# R107B.net
KiCad netlist of a schematic drawn in EAGLE
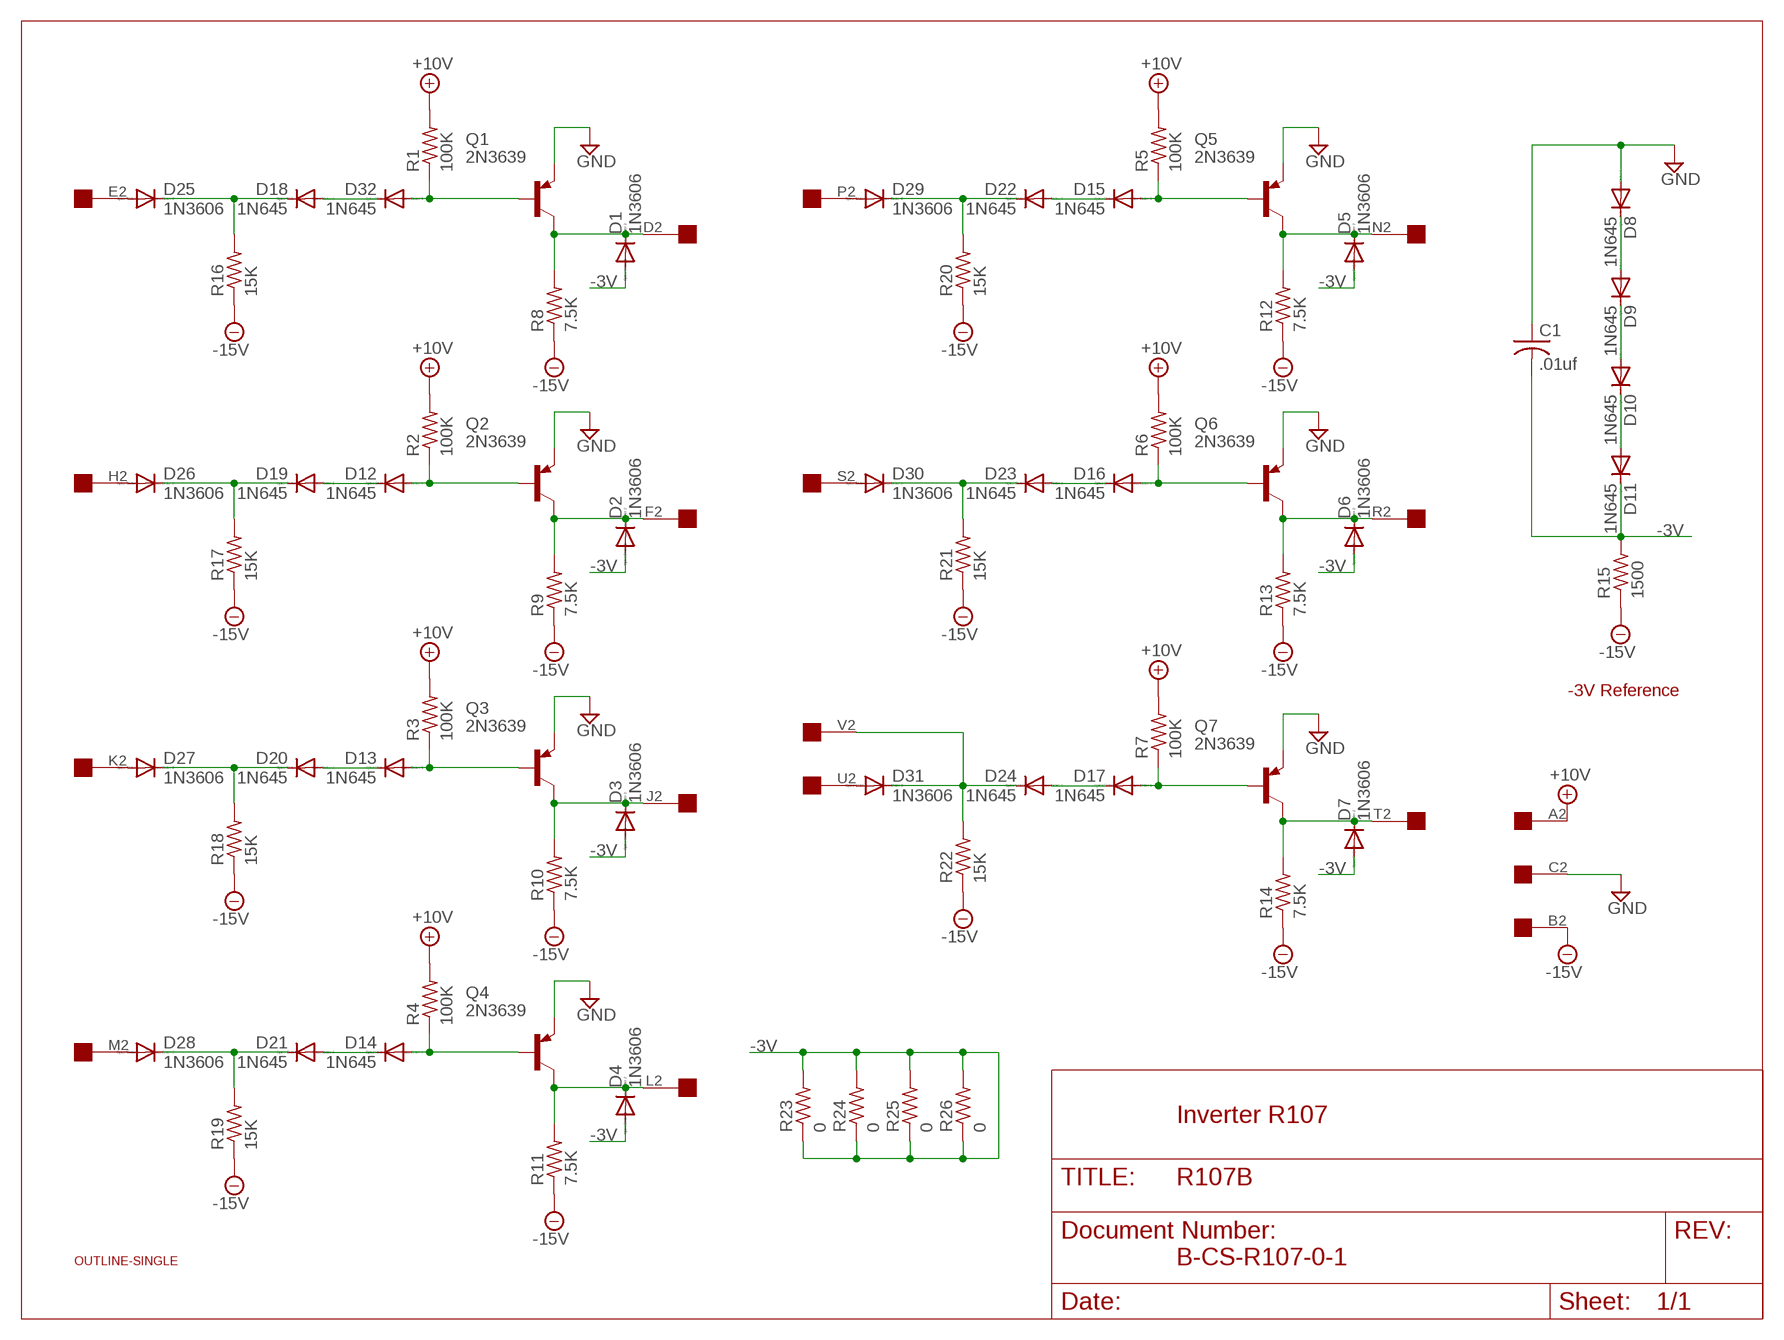
[diagram p0: schematic, sheet 1]

(export (version "E")
  (design (tool "Eeschema 10.0.6"))
  (components
    (comp (ref "C1")
      (value ".01uf")
      (footprint "eagle-import:C063-025X075")
      (libsource (lib "eagle-import") (part "C-US"))
    )
    (comp (ref "D1")
      (value "1N3606")
      (footprint "eagle-import:DO35-10")
      (libsource (lib "eagle-import") (part "1N4148DO35-10"))
    )
    (comp (ref "D2")
      (value "1N3606")
      (footprint "eagle-import:DO35-10")
      (libsource (lib "eagle-import") (part "1N4148DO35-10"))
    )
    (comp (ref "D3")
      (value "1N3606")
      (footprint "eagle-import:DO35-10")
      (libsource (lib "eagle-import") (part "1N4148DO35-10"))
    )
    (comp (ref "D4")
      (value "1N3606")
      (footprint "eagle-import:DO35-10")
      (libsource (lib "eagle-import") (part "1N4148DO35-10"))
    )
    (comp (ref "D5")
      (value "1N3606")
      (footprint "eagle-import:DO35-10")
      (libsource (lib "eagle-import") (part "1N4148DO35-10"))
    )
    (comp (ref "D6")
      (value "1N3606")
      (footprint "eagle-import:DO35-10")
      (libsource (lib "eagle-import") (part "1N4148DO35-10"))
    )
    (comp (ref "D7")
      (value "1N3606")
      (footprint "eagle-import:DO35-10")
      (libsource (lib "eagle-import") (part "1N4148DO35-10"))
    )
    (comp (ref "D8")
      (value "1N645")
      (footprint "eagle-import:DO35-10")
      (libsource (lib "eagle-import") (part "1N4148DO35-10"))
    )
    (comp (ref "D9")
      (value "1N645")
      (footprint "eagle-import:DO35-10")
      (libsource (lib "eagle-import") (part "1N4148DO35-10"))
    )
    (comp (ref "D10")
      (value "1N645")
      (footprint "eagle-import:DO35-10")
      (libsource (lib "eagle-import") (part "1N4148DO35-10"))
    )
    (comp (ref "D11")
      (value "1N645")
      (footprint "eagle-import:DO35-10")
      (libsource (lib "eagle-import") (part "1N4148DO35-10"))
    )
    (comp (ref "D12")
      (value "1N645")
      (footprint "eagle-import:DO35-10")
      (libsource (lib "eagle-import") (part "1N4148DO35-10"))
    )
    (comp (ref "D13")
      (value "1N645")
      (footprint "eagle-import:DO35-10")
      (libsource (lib "eagle-import") (part "1N4148DO35-10"))
    )
    (comp (ref "D14")
      (value "1N645")
      (footprint "eagle-import:DO35-10")
      (libsource (lib "eagle-import") (part "1N4148DO35-10"))
    )
    (comp (ref "D15")
      (value "1N645")
      (footprint "eagle-import:DO35-10")
      (libsource (lib "eagle-import") (part "1N4148DO35-10"))
    )
    (comp (ref "D16")
      (value "1N645")
      (footprint "eagle-import:DO35-10")
      (libsource (lib "eagle-import") (part "1N4148DO35-10"))
    )
    (comp (ref "D17")
      (value "1N645")
      (footprint "eagle-import:DO35-10")
      (libsource (lib "eagle-import") (part "1N4148DO35-10"))
    )
    (comp (ref "D18")
      (value "1N645")
      (footprint "eagle-import:DO35-10")
      (libsource (lib "eagle-import") (part "1N4148DO35-10"))
    )
    (comp (ref "D19")
      (value "1N645")
      (footprint "eagle-import:DO35-10")
      (libsource (lib "eagle-import") (part "1N4148DO35-10"))
    )
    (comp (ref "D20")
      (value "1N645")
      (footprint "eagle-import:DO35-10")
      (libsource (lib "eagle-import") (part "1N4148DO35-10"))
    )
    (comp (ref "D21")
      (value "1N645")
      (footprint "eagle-import:DO35-10")
      (libsource (lib "eagle-import") (part "1N4148DO35-10"))
    )
    (comp (ref "D22")
      (value "1N645")
      (footprint "eagle-import:DO35-10")
      (libsource (lib "eagle-import") (part "1N4148DO35-10"))
    )
    (comp (ref "D23")
      (value "1N645")
      (footprint "eagle-import:DO35-10")
      (libsource (lib "eagle-import") (part "1N4148DO35-10"))
    )
    (comp (ref "D24")
      (value "1N645")
      (footprint "eagle-import:DO35-10")
      (libsource (lib "eagle-import") (part "1N4148DO35-10"))
    )
    (comp (ref "D25")
      (value "1N3606")
      (footprint "eagle-import:DO35-10")
      (libsource (lib "eagle-import") (part "1N4148DO35-10"))
    )
    (comp (ref "D26")
      (value "1N3606")
      (footprint "eagle-import:DO35-10")
      (libsource (lib "eagle-import") (part "1N4148DO35-10"))
    )
    (comp (ref "D27")
      (value "1N3606")
      (footprint "eagle-import:DO35-10")
      (libsource (lib "eagle-import") (part "1N4148DO35-10"))
    )
    (comp (ref "D28")
      (value "1N3606")
      (footprint "eagle-import:DO35-10")
      (libsource (lib "eagle-import") (part "1N4148DO35-10"))
    )
    (comp (ref "D29")
      (value "1N3606")
      (footprint "eagle-import:DO35-10")
      (libsource (lib "eagle-import") (part "1N4148DO35-10"))
    )
    (comp (ref "D30")
      (value "1N3606")
      (footprint "eagle-import:DO35-10")
      (libsource (lib "eagle-import") (part "1N4148DO35-10"))
    )
    (comp (ref "D31")
      (value "1N3606")
      (footprint "eagle-import:DO35-10")
      (libsource (lib "eagle-import") (part "1N4148DO35-10"))
    )
    (comp (ref "D32")
      (value "1N645")
      (footprint "eagle-import:DO35-10")
      (libsource (lib "eagle-import") (part "1N4148DO35-10"))
    )
    (comp (ref "Q1")
      (value "2N3639")
      (footprint "eagle-import:TO39")
      (libsource (lib "eagle-import") (part "2N3637"))
    )
    (comp (ref "Q2")
      (value "2N3639")
      (footprint "eagle-import:TO39")
      (libsource (lib "eagle-import") (part "2N3637"))
    )
    (comp (ref "Q3")
      (value "2N3639")
      (footprint "eagle-import:TO39")
      (libsource (lib "eagle-import") (part "2N3637"))
    )
    (comp (ref "Q4")
      (value "2N3639")
      (footprint "eagle-import:TO39")
      (libsource (lib "eagle-import") (part "2N3637"))
    )
    (comp (ref "Q5")
      (value "2N3639")
      (footprint "eagle-import:TO39")
      (libsource (lib "eagle-import") (part "2N3637"))
    )
    (comp (ref "Q6")
      (value "2N3639")
      (footprint "eagle-import:TO39")
      (libsource (lib "eagle-import") (part "2N3637"))
    )
    (comp (ref "Q7")
      (value "2N3639")
      (footprint "eagle-import:TO39")
      (libsource (lib "eagle-import") (part "2N3637"))
    )
    (comp (ref "R1")
      (value "100K")
      (footprint "eagle-import:0207_10")
      (libsource (lib "eagle-import") (part "R-US_0207/10"))
    )
    (comp (ref "R2")
      (value "100K")
      (footprint "eagle-import:0207_10")
      (libsource (lib "eagle-import") (part "R-US_0207/10"))
    )
    (comp (ref "R3")
      (value "100K")
      (footprint "eagle-import:0207_10")
      (libsource (lib "eagle-import") (part "R-US_0207/10"))
    )
    (comp (ref "R4")
      (value "100K")
      (footprint "eagle-import:0207_10")
      (libsource (lib "eagle-import") (part "R-US_0207/10"))
    )
    (comp (ref "R5")
      (value "100K")
      (footprint "eagle-import:0207_10")
      (libsource (lib "eagle-import") (part "R-US_0207/10"))
    )
    (comp (ref "R6")
      (value "100K")
      (footprint "eagle-import:0207_10")
      (libsource (lib "eagle-import") (part "R-US_0207/10"))
    )
    (comp (ref "R7")
      (value "100K")
      (footprint "eagle-import:0207_10")
      (libsource (lib "eagle-import") (part "R-US_0207/10"))
    )
    (comp (ref "R8")
      (value "7.5K")
      (footprint "eagle-import:0207_10")
      (libsource (lib "eagle-import") (part "R-US_0207/10"))
    )
    (comp (ref "R9")
      (value "7.5K")
      (footprint "eagle-import:0207_10")
      (libsource (lib "eagle-import") (part "R-US_0207/10"))
    )
    (comp (ref "R10")
      (value "7.5K")
      (footprint "eagle-import:0207_10")
      (libsource (lib "eagle-import") (part "R-US_0207/10"))
    )
    (comp (ref "R11")
      (value "7.5K")
      (footprint "eagle-import:0207_10")
      (libsource (lib "eagle-import") (part "R-US_0207/10"))
    )
    (comp (ref "R12")
      (value "7.5K")
      (footprint "eagle-import:0207_10")
      (libsource (lib "eagle-import") (part "R-US_0207/10"))
    )
    (comp (ref "R13")
      (value "7.5K")
      (footprint "eagle-import:0207_10")
      (libsource (lib "eagle-import") (part "R-US_0207/10"))
    )
    (comp (ref "R14")
      (value "7.5K")
      (footprint "eagle-import:0207_10")
      (libsource (lib "eagle-import") (part "R-US_0207/10"))
    )
    (comp (ref "R15")
      (value "1500")
      (footprint "eagle-import:0207_10")
      (libsource (lib "eagle-import") (part "R-US_0207/10"))
    )
    (comp (ref "R16")
      (value "15K")
      (footprint "eagle-import:0207_10")
      (libsource (lib "eagle-import") (part "R-US_0207/10"))
    )
    (comp (ref "R17")
      (value "15K")
      (footprint "eagle-import:0207_10")
      (libsource (lib "eagle-import") (part "R-US_0207/10"))
    )
    (comp (ref "R18")
      (value "15K")
      (footprint "eagle-import:0207_10")
      (libsource (lib "eagle-import") (part "R-US_0207/10"))
    )
    (comp (ref "R19")
      (value "15K")
      (footprint "eagle-import:0207_10")
      (libsource (lib "eagle-import") (part "R-US_0207/10"))
    )
    (comp (ref "R20")
      (value "15K")
      (footprint "eagle-import:0207_10")
      (libsource (lib "eagle-import") (part "R-US_0207/10"))
    )
    (comp (ref "R21")
      (value "15K")
      (footprint "eagle-import:0207_10")
      (libsource (lib "eagle-import") (part "R-US_0207/10"))
    )
    (comp (ref "R22")
      (value "15K")
      (footprint "eagle-import:0207_10")
      (libsource (lib "eagle-import") (part "R-US_0207/10"))
    )
    (comp (ref "R23")
      (value "0")
      (footprint "eagle-import:0207_10")
      (libsource (lib "eagle-import") (part "R-US_0207/10"))
    )
    (comp (ref "R24")
      (value "0")
      (footprint "eagle-import:0207_10")
      (libsource (lib "eagle-import") (part "R-US_0207/10"))
    )
    (comp (ref "R25")
      (value "0")
      (footprint "eagle-import:0207_10")
      (libsource (lib "eagle-import") (part "R-US_0207/10"))
    )
    (comp (ref "R26")
      (value "0")
      (footprint "eagle-import:0207_10")
      (libsource (lib "eagle-import") (part "R-US_0207/10"))
    )
    (comp (ref "U$1")
      (value "OUTLINE-SINGLE")
      (footprint "eagle-import:SINGLE")
      (libsource (lib "eagle-import") (part "OUTLINE-SINGLE"))
    )
    (comp (ref "U$2")
      (value "EDGE-1")
      (footprint "eagle-import:EDGE-CON1")
      (libsource (lib "eagle-import") (part "EDGE-1"))
    )
  )
  (nets
    (net (code "1") (name "+10V") (class "Default")
      (node (ref "R1") (pin "2") (pinfunction "2_2") (pintype "passive"))
      (node (ref "R2") (pin "2") (pinfunction "2_2") (pintype "passive"))
      (node (ref "R3") (pin "2") (pinfunction "2_2") (pintype "passive"))
      (node (ref "R4") (pin "2") (pinfunction "2_2") (pintype "passive"))
      (node (ref "R5") (pin "2") (pinfunction "2_2") (pintype "passive"))
      (node (ref "R6") (pin "2") (pinfunction "2_2") (pintype "passive"))
      (node (ref "R7") (pin "2") (pinfunction "2_2") (pintype "passive"))
      (node (ref "U$2") (pin "A2") (pinfunction "1_A2") (pintype "bidirectional"))
    )
    (net (code "2") (name "-15V") (class "Default")
      (node (ref "R10") (pin "1") (pinfunction "1_1") (pintype "passive"))
      (node (ref "R11") (pin "1") (pinfunction "1_1") (pintype "passive"))
      (node (ref "R12") (pin "1") (pinfunction "1_1") (pintype "passive"))
      (node (ref "R13") (pin "1") (pinfunction "1_1") (pintype "passive"))
      (node (ref "R14") (pin "1") (pinfunction "1_1") (pintype "passive"))
      (node (ref "R15") (pin "1") (pinfunction "1_1") (pintype "passive"))
      (node (ref "R16") (pin "1") (pinfunction "1_1") (pintype "passive"))
      (node (ref "R17") (pin "1") (pinfunction "1_1") (pintype "passive"))
      (node (ref "R18") (pin "1") (pinfunction "1_1") (pintype "passive"))
      (node (ref "R19") (pin "1") (pinfunction "1_1") (pintype "passive"))
      (node (ref "R20") (pin "1") (pinfunction "1_1") (pintype "passive"))
      (node (ref "R21") (pin "1") (pinfunction "1_1") (pintype "passive"))
      (node (ref "R22") (pin "1") (pinfunction "1_1") (pintype "passive"))
      (node (ref "R8") (pin "1") (pinfunction "1_1") (pintype "passive"))
      (node (ref "R9") (pin "1") (pinfunction "1_1") (pintype "passive"))
      (node (ref "U$2") (pin "B2") (pinfunction "1_B2") (pintype "bidirectional"))
    )
    (net (code "3") (name "/-3V") (class "Default")
      (node (ref "C1") (pin "2") (pinfunction "2_2") (pintype "passive"))
      (node (ref "D1") (pin "A") (pinfunction "A_A") (pintype "passive"))
      (node (ref "D11") (pin "C") (pinfunction "C_C") (pintype "passive"))
      (node (ref "D2") (pin "A") (pinfunction "A_A") (pintype "passive"))
      (node (ref "D3") (pin "A") (pinfunction "A_A") (pintype "passive"))
      (node (ref "D4") (pin "A") (pinfunction "A_A") (pintype "passive"))
      (node (ref "D5") (pin "A") (pinfunction "A_A") (pintype "passive"))
      (node (ref "D6") (pin "A") (pinfunction "A_A") (pintype "passive"))
      (node (ref "D7") (pin "A") (pinfunction "A_A") (pintype "passive"))
      (node (ref "R15") (pin "2") (pinfunction "2_2") (pintype "passive"))
      (node (ref "R23") (pin "1") (pinfunction "1_1") (pintype "passive"))
      (node (ref "R23") (pin "2") (pinfunction "2_2") (pintype "passive"))
      (node (ref "R24") (pin "1") (pinfunction "1_1") (pintype "passive"))
      (node (ref "R24") (pin "2") (pinfunction "2_2") (pintype "passive"))
      (node (ref "R25") (pin "1") (pinfunction "1_1") (pintype "passive"))
      (node (ref "R25") (pin "2") (pinfunction "2_2") (pintype "passive"))
      (node (ref "R26") (pin "1") (pinfunction "1_1") (pintype "passive"))
      (node (ref "R26") (pin "2") (pinfunction "2_2") (pintype "passive"))
    )
    (net (code "4") (name "GND") (class "Default")
      (node (ref "C1") (pin "1") (pinfunction "1_1") (pintype "passive"))
      (node (ref "D8") (pin "A") (pinfunction "A_A") (pintype "passive"))
      (node (ref "Q1") (pin "1") (pinfunction "E_1") (pintype "passive"))
      (node (ref "Q2") (pin "1") (pinfunction "E_1") (pintype "passive"))
      (node (ref "Q3") (pin "1") (pinfunction "E_1") (pintype "passive"))
      (node (ref "Q4") (pin "1") (pinfunction "E_1") (pintype "passive"))
      (node (ref "Q5") (pin "1") (pinfunction "E_1") (pintype "passive"))
      (node (ref "Q6") (pin "1") (pinfunction "E_1") (pintype "passive"))
      (node (ref "Q7") (pin "1") (pinfunction "E_1") (pintype "passive"))
      (node (ref "U$2") (pin "C2") (pinfunction "1_C2") (pintype "bidirectional"))
    )
    (net (code "5") (name "Net-(D8-PadC)") (class "Default")
      (node (ref "D8") (pin "C") (pinfunction "C_C") (pintype "passive"))
      (node (ref "D9") (pin "A") (pinfunction "A_A") (pintype "passive"))
    )
    (net (code "6") (name "Net-(D10-PadA)") (class "Default")
      (node (ref "D10") (pin "A") (pinfunction "A_A") (pintype "passive"))
      (node (ref "D9") (pin "C") (pinfunction "C_C") (pintype "passive"))
    )
    (net (code "7") (name "Net-(D10-PadC)") (class "Default")
      (node (ref "D10") (pin "C") (pinfunction "C_C") (pintype "passive"))
      (node (ref "D11") (pin "A") (pinfunction "A_A") (pintype "passive"))
    )
    (net (code "8") (name "Net-(D12-PadC)") (class "Default")
      (node (ref "D12") (pin "C") (pinfunction "C_C") (pintype "passive"))
      (node (ref "D19") (pin "A") (pinfunction "A_A") (pintype "passive"))
    )
    (net (code "9") (name "Net-(D13-PadC)") (class "Default")
      (node (ref "D13") (pin "C") (pinfunction "C_C") (pintype "passive"))
      (node (ref "D20") (pin "A") (pinfunction "A_A") (pintype "passive"))
    )
    (net (code "10") (name "Net-(D14-PadC)") (class "Default")
      (node (ref "D14") (pin "C") (pinfunction "C_C") (pintype "passive"))
      (node (ref "D21") (pin "A") (pinfunction "A_A") (pintype "passive"))
    )
    (net (code "11") (name "Net-(D15-PadC)") (class "Default")
      (node (ref "D15") (pin "C") (pinfunction "C_C") (pintype "passive"))
      (node (ref "D22") (pin "A") (pinfunction "A_A") (pintype "passive"))
    )
    (net (code "12") (name "Net-(D16-PadC)") (class "Default")
      (node (ref "D16") (pin "C") (pinfunction "C_C") (pintype "passive"))
      (node (ref "D23") (pin "A") (pinfunction "A_A") (pintype "passive"))
    )
    (net (code "13") (name "Net-(D17-PadC)") (class "Default")
      (node (ref "D17") (pin "C") (pinfunction "C_C") (pintype "passive"))
      (node (ref "D24") (pin "A") (pinfunction "A_A") (pintype "passive"))
    )
    (net (code "14") (name "Net-(D18-PadA)") (class "Default")
      (node (ref "D18") (pin "A") (pinfunction "A_A") (pintype "passive"))
      (node (ref "D32") (pin "C") (pinfunction "C_C") (pintype "passive"))
    )
    (net (code "15") (name "Net-(D18-PadC)") (class "Default")
      (node (ref "D18") (pin "C") (pinfunction "C_C") (pintype "passive"))
      (node (ref "D25") (pin "C") (pinfunction "C_C") (pintype "passive"))
      (node (ref "R16") (pin "2") (pinfunction "2_2") (pintype "passive"))
    )
    (net (code "16") (name "Net-(D19-PadC)") (class "Default")
      (node (ref "D19") (pin "C") (pinfunction "C_C") (pintype "passive"))
      (node (ref "D26") (pin "C") (pinfunction "C_C") (pintype "passive"))
      (node (ref "R17") (pin "2") (pinfunction "2_2") (pintype "passive"))
    )
    (net (code "17") (name "Net-(D20-PadC)") (class "Default")
      (node (ref "D20") (pin "C") (pinfunction "C_C") (pintype "passive"))
      (node (ref "D27") (pin "C") (pinfunction "C_C") (pintype "passive"))
      (node (ref "R18") (pin "2") (pinfunction "2_2") (pintype "passive"))
    )
    (net (code "18") (name "Net-(D21-PadC)") (class "Default")
      (node (ref "D21") (pin "C") (pinfunction "C_C") (pintype "passive"))
      (node (ref "D28") (pin "C") (pinfunction "C_C") (pintype "passive"))
      (node (ref "R19") (pin "2") (pinfunction "2_2") (pintype "passive"))
    )
    (net (code "19") (name "Net-(D22-PadC)") (class "Default")
      (node (ref "D22") (pin "C") (pinfunction "C_C") (pintype "passive"))
      (node (ref "D29") (pin "C") (pinfunction "C_C") (pintype "passive"))
      (node (ref "R20") (pin "2") (pinfunction "2_2") (pintype "passive"))
    )
    (net (code "20") (name "Net-(D23-PadC)") (class "Default")
      (node (ref "D23") (pin "C") (pinfunction "C_C") (pintype "passive"))
      (node (ref "D30") (pin "C") (pinfunction "C_C") (pintype "passive"))
      (node (ref "R21") (pin "2") (pinfunction "2_2") (pintype "passive"))
    )
    (net (code "21") (name "Net-(Q1-B)") (class "Default")
      (node (ref "D32") (pin "A") (pinfunction "A_A") (pintype "passive"))
      (node (ref "Q1") (pin "2") (pinfunction "B_2") (pintype "passive"))
      (node (ref "R1") (pin "1") (pinfunction "1_1") (pintype "passive"))
    )
    (net (code "22") (name "Net-(Q1-C)") (class "Default")
      (node (ref "D1") (pin "C") (pinfunction "C_C") (pintype "passive"))
      (node (ref "Q1") (pin "3") (pinfunction "C_3") (pintype "passive"))
      (node (ref "R8") (pin "2") (pinfunction "2_2") (pintype "passive"))
      (node (ref "U$2") (pin "D2") (pinfunction "1_D2") (pintype "bidirectional"))
    )
    (net (code "23") (name "Net-(Q2-B)") (class "Default")
      (node (ref "D12") (pin "A") (pinfunction "A_A") (pintype "passive"))
      (node (ref "Q2") (pin "2") (pinfunction "B_2") (pintype "passive"))
      (node (ref "R2") (pin "1") (pinfunction "1_1") (pintype "passive"))
    )
    (net (code "24") (name "Net-(Q2-C)") (class "Default")
      (node (ref "D2") (pin "C") (pinfunction "C_C") (pintype "passive"))
      (node (ref "Q2") (pin "3") (pinfunction "C_3") (pintype "passive"))
      (node (ref "R9") (pin "2") (pinfunction "2_2") (pintype "passive"))
      (node (ref "U$2") (pin "F2") (pinfunction "1_F2") (pintype "bidirectional"))
    )
    (net (code "25") (name "Net-(Q3-B)") (class "Default")
      (node (ref "D13") (pin "A") (pinfunction "A_A") (pintype "passive"))
      (node (ref "Q3") (pin "2") (pinfunction "B_2") (pintype "passive"))
      (node (ref "R3") (pin "1") (pinfunction "1_1") (pintype "passive"))
    )
    (net (code "26") (name "Net-(Q3-C)") (class "Default")
      (node (ref "D3") (pin "C") (pinfunction "C_C") (pintype "passive"))
      (node (ref "Q3") (pin "3") (pinfunction "C_3") (pintype "passive"))
      (node (ref "R10") (pin "2") (pinfunction "2_2") (pintype "passive"))
      (node (ref "U$2") (pin "J2") (pinfunction "1_J2") (pintype "bidirectional"))
    )
    (net (code "27") (name "Net-(Q4-B)") (class "Default")
      (node (ref "D14") (pin "A") (pinfunction "A_A") (pintype "passive"))
      (node (ref "Q4") (pin "2") (pinfunction "B_2") (pintype "passive"))
      (node (ref "R4") (pin "1") (pinfunction "1_1") (pintype "passive"))
    )
    (net (code "28") (name "Net-(Q4-C)") (class "Default")
      (node (ref "D4") (pin "C") (pinfunction "C_C") (pintype "passive"))
      (node (ref "Q4") (pin "3") (pinfunction "C_3") (pintype "passive"))
      (node (ref "R11") (pin "2") (pinfunction "2_2") (pintype "passive"))
      (node (ref "U$2") (pin "L2") (pinfunction "1_L2") (pintype "bidirectional"))
    )
    (net (code "29") (name "Net-(Q5-B)") (class "Default")
      (node (ref "D15") (pin "A") (pinfunction "A_A") (pintype "passive"))
      (node (ref "Q5") (pin "2") (pinfunction "B_2") (pintype "passive"))
      (node (ref "R5") (pin "1") (pinfunction "1_1") (pintype "passive"))
    )
    (net (code "30") (name "Net-(Q5-C)") (class "Default")
      (node (ref "D5") (pin "C") (pinfunction "C_C") (pintype "passive"))
      (node (ref "Q5") (pin "3") (pinfunction "C_3") (pintype "passive"))
      (node (ref "R12") (pin "2") (pinfunction "2_2") (pintype "passive"))
      (node (ref "U$2") (pin "N2") (pinfunction "1_N2") (pintype "bidirectional"))
    )
    (net (code "31") (name "Net-(Q6-B)") (class "Default")
      (node (ref "D16") (pin "A") (pinfunction "A_A") (pintype "passive"))
      (node (ref "Q6") (pin "2") (pinfunction "B_2") (pintype "passive"))
      (node (ref "R6") (pin "1") (pinfunction "1_1") (pintype "passive"))
    )
    (net (code "32") (name "Net-(Q6-C)") (class "Default")
      (node (ref "D6") (pin "C") (pinfunction "C_C") (pintype "passive"))
      (node (ref "Q6") (pin "3") (pinfunction "C_3") (pintype "passive"))
      (node (ref "R13") (pin "2") (pinfunction "2_2") (pintype "passive"))
      (node (ref "U$2") (pin "R2") (pinfunction "1_R2") (pintype "bidirectional"))
    )
    (net (code "33") (name "Net-(Q7-B)") (class "Default")
      (node (ref "D17") (pin "A") (pinfunction "A_A") (pintype "passive"))
      (node (ref "Q7") (pin "2") (pinfunction "B_2") (pintype "passive"))
      (node (ref "R7") (pin "1") (pinfunction "1_1") (pintype "passive"))
    )
    (net (code "34") (name "Net-(Q7-C)") (class "Default")
      (node (ref "D7") (pin "C") (pinfunction "C_C") (pintype "passive"))
      (node (ref "Q7") (pin "3") (pinfunction "C_3") (pintype "passive"))
      (node (ref "R14") (pin "2") (pinfunction "2_2") (pintype "passive"))
      (node (ref "U$2") (pin "T2") (pinfunction "1_T2") (pintype "bidirectional"))
    )
    (net (code "35") (name "Net-(U$2E-1)") (class "Default")
      (node (ref "D25") (pin "A") (pinfunction "A_A") (pintype "passive"))
      (node (ref "U$2") (pin "E2") (pinfunction "1_E2") (pintype "bidirectional"))
    )
    (net (code "36") (name "Net-(U$2G-1)") (class "Default")
      (node (ref "D26") (pin "A") (pinfunction "A_A") (pintype "passive"))
      (node (ref "U$2") (pin "H2") (pinfunction "1_H2") (pintype "bidirectional"))
    )
    (net (code "37") (name "Net-(U$2I-1)") (class "Default")
      (node (ref "D27") (pin "A") (pinfunction "A_A") (pintype "passive"))
      (node (ref "U$2") (pin "K2") (pinfunction "1_K2") (pintype "bidirectional"))
    )
    (net (code "38") (name "Net-(U$2K-1)") (class "Default")
      (node (ref "D28") (pin "A") (pinfunction "A_A") (pintype "passive"))
      (node (ref "U$2") (pin "M2") (pinfunction "1_M2") (pintype "bidirectional"))
    )
    (net (code "39") (name "Net-(U$2M-1)") (class "Default")
      (node (ref "D29") (pin "A") (pinfunction "A_A") (pintype "passive"))
      (node (ref "U$2") (pin "P2") (pinfunction "1_P2") (pintype "bidirectional"))
    )
    (net (code "40") (name "Net-(U$2O-1)") (class "Default")
      (node (ref "D30") (pin "A") (pinfunction "A_A") (pintype "passive"))
      (node (ref "U$2") (pin "S2") (pinfunction "1_S2") (pintype "bidirectional"))
    )
    (net (code "41") (name "Net-(U$2Q-1)") (class "Default")
      (node (ref "D31") (pin "A") (pinfunction "A_A") (pintype "passive"))
      (node (ref "U$2") (pin "U2") (pinfunction "1_U2") (pintype "bidirectional"))
    )
    (net (code "42") (name "Net-(U$2R-1)") (class "Default")
      (node (ref "D24") (pin "C") (pinfunction "C_C") (pintype "passive"))
      (node (ref "D31") (pin "C") (pinfunction "C_C") (pintype "passive"))
      (node (ref "R22") (pin "2") (pinfunction "2_2") (pintype "passive"))
      (node (ref "U$2") (pin "V2") (pinfunction "1_V2") (pintype "bidirectional"))
    )
  )
)
